# TEST_USB.net
KiCad netlist of a schematic drawn in Altium Designer
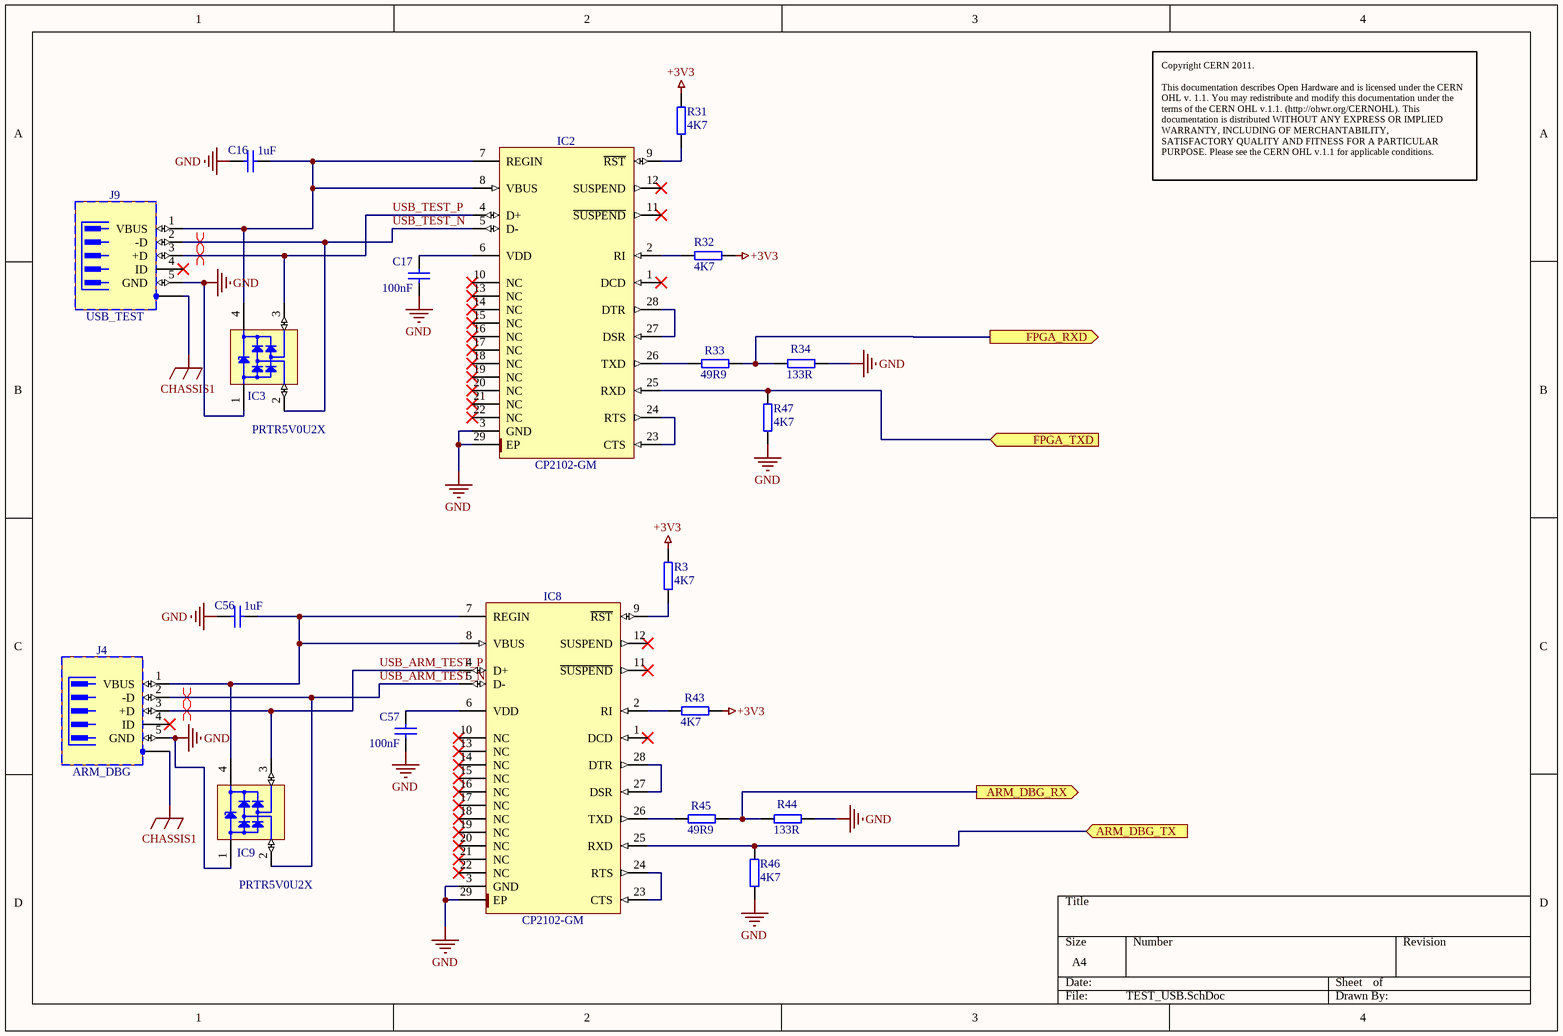
[diagram p0: TEST_USB.SchDoc]

(export (version "E")
  (design (tool "Eeschema 10.0.6"))
  (components
    (comp (ref "C16")
      (value "1uF")
      (footprint "CC1608-0603")
      (description "Capacitor")
      (fields
        (field (name "TOLERANCE") "±10%")
        (field (name "VOLTAGE") "25V")
        (field (name "PUBLISHER") "Altium Limited")
      )
      (libsource (lib "wr_switch") (part "Cap"))
    )
    (comp (ref "C17")
      (value "100nF")
      (footprint "CC1608-0603")
      (description "Capacitor")
      (fields
        (field (name "TOLERANCE") "±10%")
        (field (name "VOLTAGE") "16V")
        (field (name "PUBLISHER") "Altium Limited")
      )
      (libsource (lib "wr_switch") (part "Cap"))
    )
    (comp (ref "C56")
      (value "1uF")
      (footprint "CC1608-0603")
      (description "Capacitor")
      (fields
        (field (name "TOLERANCE") "±10%")
        (field (name "VOLTAGE") "25V")
        (field (name "PUBLISHER") "Altium Limited")
      )
      (libsource (lib "wr_switch") (part "Cap"))
    )
    (comp (ref "C57")
      (value "100nF")
      (footprint "CC1608-0603")
      (description "Capacitor")
      (fields
        (field (name "TOLERANCE") "±10%")
        (field (name "VOLTAGE") "16V")
        (field (name "PUBLISHER") "Altium Limited")
      )
      (libsource (lib "wr_switch") (part "Cap"))
    )
    (comp (ref "IC2")
      (value "CP2102-GM")
      (footprint "7S_WR:QFN50P500X500X100-29N-S335")
      (description "Single-Chip USB to UART Bridge")
      (fields (field (name "MANUFACTURER") "SILICON LABS") (field (name "AUTHOR") "CERN DEM JLC"))
      (libsource (lib "wr_switch") (part "CP2102-GM"))
    )
    (comp (ref "IC3")
      (value "PRTR5V0U2X")
      (footprint "7S_WR:SOT190P230X110-4N")
      (description "Ultra Low Capacitance Double Rail-to-Rail ESD Protection Diode")
      (fields
        (field (name "VOLTAGE") "5.5V")
        (field (name "MANUFACTURER") "PHILIPS NXP")
        (field (name "AUTHOR") "CERN DEM JLC")
      )
      (libsource (lib "wr_switch") (part "PRTR5V0U2X"))
    )
    (comp (ref "IC8")
      (value "CP2102-GM")
      (footprint "7S_WR:QFN50P500X500X100-29N-S335")
      (description "Single-Chip USB to UART Bridge")
      (fields (field (name "MANUFACTURER") "SILICON LABS") (field (name "AUTHOR") "CERN DEM JLC"))
      (libsource (lib "wr_switch") (part "CP2102-GM"))
    )
    (comp (ref "IC9")
      (value "PRTR5V0U2X")
      (footprint "7S_WR:SOT190P230X110-4N")
      (description "Ultra Low Capacitance Double Rail-to-Rail ESD Protection Diode")
      (fields
        (field (name "VOLTAGE") "5.5V")
        (field (name "MANUFACTURER") "PHILIPS NXP")
        (field (name "AUTHOR") "CERN DEM JLC")
      )
      (libsource (lib "wr_switch") (part "PRTR5V0U2X"))
    )
    (comp (ref "J4")
      (value "ARM_DBG")
      (footprint "7S_WR:TYCO_1734035-1")
      (description "5 Pin + 1 Shield Mini USB Type B Receptacle")
      (fields
        (field (name "PART NUMBER") "TYCO_1734035-1")
        (field (name "MANUFACTURER") "TYCO ELECTRONICS")
        (field (name "AUTHOR") "CERN DEM JLC")
      )
      (libsource (lib "wr_switch") (part "TYCO_1734035-1"))
    )
    (comp (ref "J9")
      (value "USB_TEST")
      (footprint "7S_WR:TYCO_1734035-1")
      (description "5 Pin + 1 Shield Mini USB Type B Receptacle")
      (fields
        (field (name "PART NUMBER") "TYCO_1734035-1")
        (field (name "MANUFACTURER") "TYCO ELECTRONICS")
        (field (name "AUTHOR") "CERN DEM JLC")
      )
      (libsource (lib "wr_switch") (part "TYCO_1734035-1"))
    )
    (comp (ref "R3")
      (value "4K7")
      (footprint "0603")
      (description "SMD Resistor")
      (fields (field (name "TOLERANCE") "±1%"))
      (libsource (lib "wr_switch") (part "RES_SMD"))
    )
    (comp (ref "R31")
      (value "4K7")
      (footprint "0603")
      (description "SMD Resistor")
      (fields (field (name "TOLERANCE") "±1%"))
      (libsource (lib "wr_switch") (part "RES_SMD"))
    )
    (comp (ref "R32")
      (value "4K7")
      (footprint "0603")
      (description "SMD Resistor")
      (fields (field (name "TOLERANCE") "±1%"))
      (libsource (lib "wr_switch") (part "RES_SMD"))
    )
    (comp (ref "R33")
      (value "49R9")
      (footprint "0603")
      (description "SMD Resistor")
      (fields (field (name "TOLERANCE") "±1%"))
      (libsource (lib "wr_switch") (part "RES_SMD"))
    )
    (comp (ref "R34")
      (value "133R")
      (footprint "0603")
      (description "SMD Resistor")
      (fields (field (name "TOLERANCE") "±1%"))
      (libsource (lib "wr_switch") (part "RES_SMD"))
    )
    (comp (ref "R43")
      (value "4K7")
      (footprint "0603")
      (description "SMD Resistor")
      (fields (field (name "TOLERANCE") "±1%"))
      (libsource (lib "wr_switch") (part "RES_SMD"))
    )
    (comp (ref "R44")
      (value "133R")
      (footprint "0603")
      (description "SMD Resistor")
      (fields (field (name "TOLERANCE") "±1%"))
      (libsource (lib "wr_switch") (part "RES_SMD"))
    )
    (comp (ref "R45")
      (value "49R9")
      (footprint "0603")
      (description "SMD Resistor")
      (fields (field (name "TOLERANCE") "±1%"))
      (libsource (lib "wr_switch") (part "RES_SMD"))
    )
    (comp (ref "R46")
      (value "4K7")
      (footprint "0603")
      (description "SMD Resistor")
      (fields (field (name "TOLERANCE") "±1%"))
      (libsource (lib "wr_switch") (part "RES_SMD"))
    )
    (comp (ref "R47")
      (value "4K7")
      (footprint "0603")
      (description "SMD Resistor")
      (fields (field (name "TOLERANCE") "±1%"))
      (libsource (lib "wr_switch") (part "RES_SMD"))
    )
  )
  (nets
    (net (code "1") (name "+3V3") (class "Default")
      (node (ref "R3") (pin "1") (pinfunction "1_1") (pintype "passive"))
      (node (ref "R31") (pin "1") (pinfunction "1_1") (pintype "passive"))
      (node (ref "R32") (pin "2") (pinfunction "2_2") (pintype "passive"))
      (node (ref "R43") (pin "2") (pinfunction "2_2") (pintype "passive"))
    )
    (net (code "2") (name "/ARM_DBG_RX") (class "Default")
      (node (ref "R44") (pin "1") (pinfunction "1_1") (pintype "passive"))
      (node (ref "R45") (pin "2") (pinfunction "2_2") (pintype "passive"))
    )
    (net (code "3") (name "/ARM_DBG_TX") (class "Default")
      (node (ref "IC8") (pin "25") (pinfunction "RXD_25") (pintype "input"))
      (node (ref "R46") (pin "1") (pinfunction "1_1") (pintype "passive"))
    )
    (net (code "4") (name "/FPGA_RXD") (class "Default")
      (node (ref "R33") (pin "2") (pinfunction "2_2") (pintype "passive"))
      (node (ref "R34") (pin "1") (pinfunction "1_1") (pintype "passive"))
    )
    (net (code "5") (name "/FPGA_TXD") (class "Default")
      (node (ref "IC2") (pin "25") (pinfunction "RXD_25") (pintype "input"))
      (node (ref "R47") (pin "1") (pinfunction "1_1") (pintype "passive"))
    )
    (net (code "6") (name "/USB_ARM_TEST_N") (class "Default")
      (node (ref "IC8") (pin "5") (pinfunction "D-_5") (pintype "bidirectional"))
      (node (ref "IC9") (pin "2") (pinfunction "I/O1_2") (pintype "bidirectional"))
      (node (ref "J4") (pin "2") (pinfunction "-D_2") (pintype "bidirectional"))
    )
    (net (code "7") (name "/USB_ARM_TEST_P") (class "Default")
      (node (ref "IC8") (pin "4") (pinfunction "D+_4") (pintype "bidirectional"))
      (node (ref "IC9") (pin "3") (pinfunction "I/O2_3") (pintype "bidirectional"))
      (node (ref "J4") (pin "3") (pinfunction "+D_3") (pintype "bidirectional"))
    )
    (net (code "8") (name "/USB_TEST_N") (class "Default")
      (node (ref "IC2") (pin "5") (pinfunction "D-_5") (pintype "bidirectional"))
      (node (ref "IC3") (pin "2") (pinfunction "I/O1_2") (pintype "bidirectional"))
      (node (ref "J9") (pin "2") (pinfunction "-D_2") (pintype "bidirectional"))
    )
    (net (code "9") (name "/USB_TEST_P") (class "Default")
      (node (ref "IC2") (pin "4") (pinfunction "D+_4") (pintype "bidirectional"))
      (node (ref "IC3") (pin "3") (pinfunction "I/O2_3") (pintype "bidirectional"))
      (node (ref "J9") (pin "3") (pinfunction "+D_3") (pintype "bidirectional"))
    )
    (net (code "10") (name "CHASSIS1") (class "Default")
      (node (ref "J4") (pin "6") (pinfunction "SH_6") (pintype "power_in"))
      (node (ref "J9") (pin "6") (pinfunction "SH_6") (pintype "power_in"))
    )
    (net (code "11") (name "GND") (class "Default")
      (node (ref "C16") (pin "1") (pinfunction "1_1") (pintype "passive"))
      (node (ref "C17") (pin "2") (pinfunction "2_2") (pintype "passive"))
      (node (ref "C56") (pin "1") (pinfunction "1_1") (pintype "passive"))
      (node (ref "C57") (pin "2") (pinfunction "2_2") (pintype "passive"))
      (node (ref "IC2") (pin "29") (pinfunction "EP_29") (pintype "power_in"))
      (node (ref "IC2") (pin "3") (pinfunction "GND_3") (pintype "power_in"))
      (node (ref "IC3") (pin "1") (pinfunction "GND_1") (pintype "power_in"))
      (node (ref "IC8") (pin "29") (pinfunction "EP_29") (pintype "power_in"))
      (node (ref "IC8") (pin "3") (pinfunction "GND_3") (pintype "power_in"))
      (node (ref "IC9") (pin "1") (pinfunction "GND_1") (pintype "power_in"))
      (node (ref "J4") (pin "5") (pinfunction "GND_5") (pintype "bidirectional"))
      (node (ref "J9") (pin "5") (pinfunction "GND_5") (pintype "bidirectional"))
      (node (ref "R34") (pin "2") (pinfunction "2_2") (pintype "passive"))
      (node (ref "R44") (pin "2") (pinfunction "2_2") (pintype "passive"))
      (node (ref "R46") (pin "2") (pinfunction "2_2") (pintype "passive"))
      (node (ref "R47") (pin "2") (pinfunction "2_2") (pintype "passive"))
    )
    (net (code "12") (name "Net-(IC2-CTS)") (class "Default")
      (node (ref "IC2") (pin "23") (pinfunction "CTS_23") (pintype "input"))
      (node (ref "IC2") (pin "24") (pinfunction "RTS_24") (pintype "output"))
    )
    (net (code "13") (name "Net-(IC2-DSR)") (class "Default")
      (node (ref "IC2") (pin "27") (pinfunction "DSR_27") (pintype "input"))
      (node (ref "IC2") (pin "28") (pinfunction "DTR_28") (pintype "output"))
    )
    (net (code "14") (name "Net-(IC2-REGIN)") (class "Default")
      (node (ref "C16") (pin "2") (pinfunction "2_2") (pintype "passive"))
      (node (ref "IC2") (pin "7") (pinfunction "REGIN_7") (pintype "power_in"))
      (node (ref "IC2") (pin "8") (pinfunction "VBUS_8") (pintype "input"))
      (node (ref "IC3") (pin "4") (pinfunction "VCC_4") (pintype "power_in"))
      (node (ref "J9") (pin "1") (pinfunction "VBUS_1") (pintype "bidirectional"))
    )
    (net (code "15") (name "Net-(IC2-RI)") (class "Default")
      (node (ref "IC2") (pin "2") (pinfunction "RI_2") (pintype "input"))
      (node (ref "R32") (pin "1") (pinfunction "1_1") (pintype "passive"))
    )
    (net (code "16") (name "Net-(IC2-TXD)") (class "Default")
      (node (ref "IC2") (pin "26") (pinfunction "TXD_26") (pintype "output"))
      (node (ref "R33") (pin "1") (pinfunction "1_1") (pintype "passive"))
    )
    (net (code "17") (name "Net-(IC2-VDD)") (class "Default")
      (node (ref "C17") (pin "1") (pinfunction "1_1") (pintype "passive"))
      (node (ref "IC2") (pin "6") (pinfunction "VDD_6") (pintype "power_in"))
    )
    (net (code "18") (name "Net-(IC2-~{RST})") (class "Default")
      (node (ref "IC2") (pin "9") (pinfunction "~{RST}_9") (pintype "bidirectional"))
      (node (ref "R31") (pin "2") (pinfunction "2_2") (pintype "passive"))
    )
    (net (code "19") (name "Net-(IC8-CTS)") (class "Default")
      (node (ref "IC8") (pin "23") (pinfunction "CTS_23") (pintype "input"))
      (node (ref "IC8") (pin "24") (pinfunction "RTS_24") (pintype "output"))
    )
    (net (code "20") (name "Net-(IC8-DSR)") (class "Default")
      (node (ref "IC8") (pin "27") (pinfunction "DSR_27") (pintype "input"))
      (node (ref "IC8") (pin "28") (pinfunction "DTR_28") (pintype "output"))
    )
    (net (code "21") (name "Net-(IC8-REGIN)") (class "Default")
      (node (ref "C56") (pin "2") (pinfunction "2_2") (pintype "passive"))
      (node (ref "IC8") (pin "7") (pinfunction "REGIN_7") (pintype "power_in"))
      (node (ref "IC8") (pin "8") (pinfunction "VBUS_8") (pintype "input"))
      (node (ref "IC9") (pin "4") (pinfunction "VCC_4") (pintype "power_in"))
      (node (ref "J4") (pin "1") (pinfunction "VBUS_1") (pintype "bidirectional"))
    )
    (net (code "22") (name "Net-(IC8-RI)") (class "Default")
      (node (ref "IC8") (pin "2") (pinfunction "RI_2") (pintype "input"))
      (node (ref "R43") (pin "1") (pinfunction "1_1") (pintype "passive"))
    )
    (net (code "23") (name "Net-(IC8-TXD)") (class "Default")
      (node (ref "IC8") (pin "26") (pinfunction "TXD_26") (pintype "output"))
      (node (ref "R45") (pin "1") (pinfunction "1_1") (pintype "passive"))
    )
    (net (code "24") (name "Net-(IC8-VDD)") (class "Default")
      (node (ref "C57") (pin "1") (pinfunction "1_1") (pintype "passive"))
      (node (ref "IC8") (pin "6") (pinfunction "VDD_6") (pintype "power_in"))
    )
    (net (code "25") (name "Net-(IC8-~{RST})") (class "Default")
      (node (ref "IC8") (pin "9") (pinfunction "~{RST}_9") (pintype "bidirectional"))
      (node (ref "R3") (pin "2") (pinfunction "2_2") (pintype "passive"))
    )
    (net (code "26") (name "unconnected-(IC2-DCD-Pad1)") (class "Default")
      (node (ref "IC2") (pin "1") (pinfunction "DCD_1") (pintype "input+no_connect"))
    )
    (net (code "27") (name "unconnected-(IC2-NC-Pad10)") (class "Default")
      (node (ref "IC2") (pin "10") (pinfunction "NC_10") (pintype "passive+no_connect"))
    )
    (net (code "28") (name "unconnected-(IC2-NC-Pad13)") (class "Default")
      (node (ref "IC2") (pin "13") (pinfunction "NC_13") (pintype "passive+no_connect"))
    )
    (net (code "29") (name "unconnected-(IC2-NC-Pad14)") (class "Default")
      (node (ref "IC2") (pin "14") (pinfunction "NC_14") (pintype "passive+no_connect"))
    )
    (net (code "30") (name "unconnected-(IC2-NC-Pad15)") (class "Default")
      (node (ref "IC2") (pin "15") (pinfunction "NC_15") (pintype "passive+no_connect"))
    )
    (net (code "31") (name "unconnected-(IC2-NC-Pad16)") (class "Default")
      (node (ref "IC2") (pin "16") (pinfunction "NC_16") (pintype "passive+no_connect"))
    )
    (net (code "32") (name "unconnected-(IC2-NC-Pad17)") (class "Default")
      (node (ref "IC2") (pin "17") (pinfunction "NC_17") (pintype "passive+no_connect"))
    )
    (net (code "33") (name "unconnected-(IC2-NC-Pad18)") (class "Default")
      (node (ref "IC2") (pin "18") (pinfunction "NC_18") (pintype "passive+no_connect"))
    )
    (net (code "34") (name "unconnected-(IC2-NC-Pad19)") (class "Default")
      (node (ref "IC2") (pin "19") (pinfunction "NC_19") (pintype "passive+no_connect"))
    )
    (net (code "35") (name "unconnected-(IC2-NC-Pad20)") (class "Default")
      (node (ref "IC2") (pin "20") (pinfunction "NC_20") (pintype "passive+no_connect"))
    )
    (net (code "36") (name "unconnected-(IC2-NC-Pad21)") (class "Default")
      (node (ref "IC2") (pin "21") (pinfunction "NC_21") (pintype "passive+no_connect"))
    )
    (net (code "37") (name "unconnected-(IC2-NC-Pad22)") (class "Default")
      (node (ref "IC2") (pin "22") (pinfunction "NC_22") (pintype "passive+no_connect"))
    )
    (net (code "38") (name "unconnected-(IC2-SUSPEND-Pad12)") (class "Default")
      (node (ref "IC2") (pin "12") (pinfunction "SUSPEND_12") (pintype "output+no_connect"))
    )
    (net (code "39") (name "unconnected-(IC2-~{SUSPEND}-Pad11)") (class "Default")
      (node (ref "IC2") (pin "11") (pinfunction "~{SUSPEND}_11") (pintype "output+no_connect"))
    )
    (net (code "40") (name "unconnected-(IC8-DCD-Pad1)") (class "Default")
      (node (ref "IC8") (pin "1") (pinfunction "DCD_1") (pintype "input+no_connect"))
    )
    (net (code "41") (name "unconnected-(IC8-NC-Pad10)") (class "Default")
      (node (ref "IC8") (pin "10") (pinfunction "NC_10") (pintype "passive+no_connect"))
    )
    (net (code "42") (name "unconnected-(IC8-NC-Pad13)") (class "Default")
      (node (ref "IC8") (pin "13") (pinfunction "NC_13") (pintype "passive+no_connect"))
    )
    (net (code "43") (name "unconnected-(IC8-NC-Pad14)") (class "Default")
      (node (ref "IC8") (pin "14") (pinfunction "NC_14") (pintype "passive+no_connect"))
    )
    (net (code "44") (name "unconnected-(IC8-NC-Pad15)") (class "Default")
      (node (ref "IC8") (pin "15") (pinfunction "NC_15") (pintype "passive+no_connect"))
    )
    (net (code "45") (name "unconnected-(IC8-NC-Pad16)") (class "Default")
      (node (ref "IC8") (pin "16") (pinfunction "NC_16") (pintype "passive+no_connect"))
    )
    (net (code "46") (name "unconnected-(IC8-NC-Pad17)") (class "Default")
      (node (ref "IC8") (pin "17") (pinfunction "NC_17") (pintype "passive+no_connect"))
    )
    (net (code "47") (name "unconnected-(IC8-NC-Pad18)") (class "Default")
      (node (ref "IC8") (pin "18") (pinfunction "NC_18") (pintype "passive+no_connect"))
    )
    (net (code "48") (name "unconnected-(IC8-NC-Pad19)") (class "Default")
      (node (ref "IC8") (pin "19") (pinfunction "NC_19") (pintype "passive+no_connect"))
    )
    (net (code "49") (name "unconnected-(IC8-NC-Pad20)") (class "Default")
      (node (ref "IC8") (pin "20") (pinfunction "NC_20") (pintype "passive+no_connect"))
    )
    (net (code "50") (name "unconnected-(IC8-NC-Pad21)") (class "Default")
      (node (ref "IC8") (pin "21") (pinfunction "NC_21") (pintype "passive+no_connect"))
    )
    (net (code "51") (name "unconnected-(IC8-NC-Pad22)") (class "Default")
      (node (ref "IC8") (pin "22") (pinfunction "NC_22") (pintype "passive+no_connect"))
    )
    (net (code "52") (name "unconnected-(IC8-SUSPEND-Pad12)") (class "Default")
      (node (ref "IC8") (pin "12") (pinfunction "SUSPEND_12") (pintype "output+no_connect"))
    )
    (net (code "53") (name "unconnected-(IC8-~{SUSPEND}-Pad11)") (class "Default")
      (node (ref "IC8") (pin "11") (pinfunction "~{SUSPEND}_11") (pintype "output+no_connect"))
    )
    (net (code "54") (name "unconnected-(J4-ID-Pad4)") (class "Default")
      (node (ref "J4") (pin "4") (pinfunction "ID_4") (pintype "passive+no_connect"))
    )
    (net (code "55") (name "unconnected-(J9-ID-Pad4)") (class "Default")
      (node (ref "J9") (pin "4") (pinfunction "ID_4") (pintype "passive+no_connect"))
    )
  )
)
